# Prova02.net
KiCad netlist of a schematic drawn in EAGLE
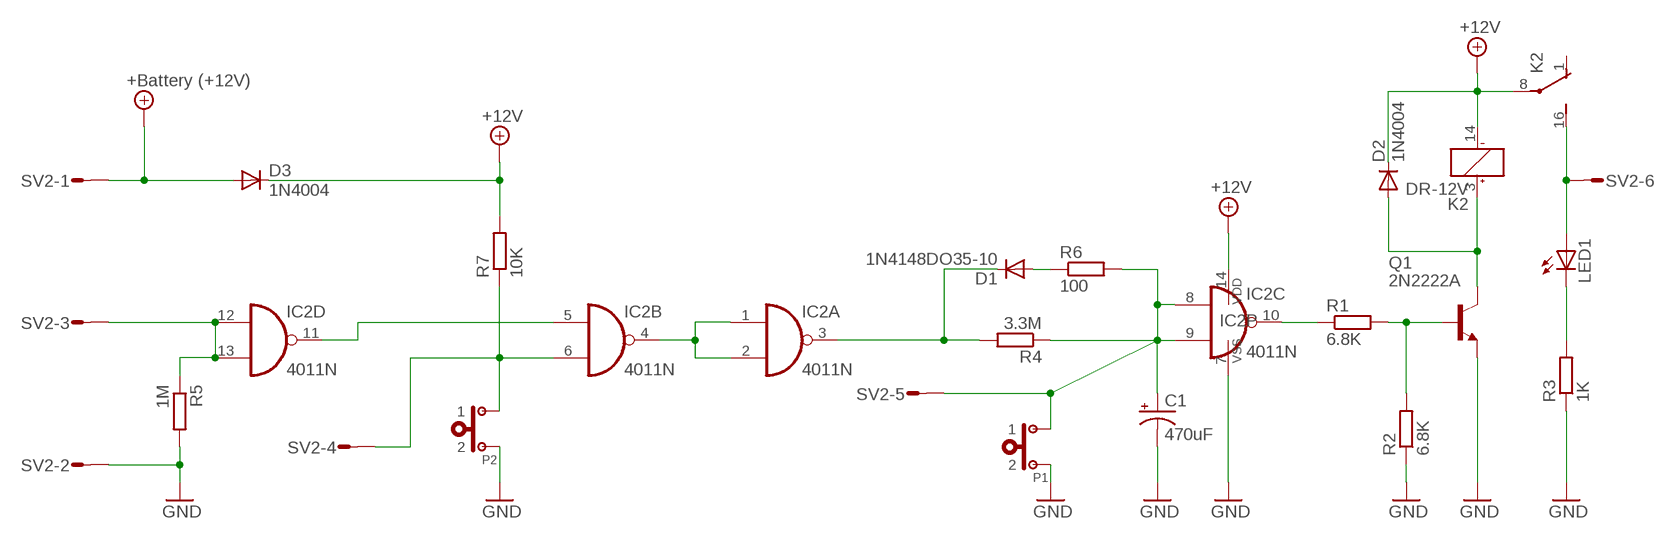
[diagram p0: schematic, sheet 1]

(export (version "E")
  (design (tool "Eeschema 10.0.6"))
  (components
    (comp (ref "C1")
      (value "470uF")
      (footprint "eagle-import:E3,5-8")
      (libsource (lib "eagle-import") (part "CPOL-USE3.5-8"))
    )
    (comp (ref "D1")
      (value "1N4148DO35-10")
      (footprint "eagle-import:DO35-10")
      (libsource (lib "eagle-import") (part "1N4148DO35-10"))
    )
    (comp (ref "D2")
      (value "1N4004")
      (footprint "eagle-import:DO41-10")
      (libsource (lib "eagle-import") (part "1N4004"))
    )
    (comp (ref "D3")
      (value "1N4004")
      (footprint "eagle-import:DO41-10")
      (libsource (lib "eagle-import") (part "1N4004"))
    )
    (comp (ref "IC2")
      (value "4011N")
      (footprint "eagle-import:DIL14")
      (libsource (lib "eagle-import") (part "4011N"))
    )
    (comp (ref "K2")
      (value "DR-12V")
      (footprint "eagle-import:DR-1")
      (libsource (lib "eagle-import") (part "DR-V12"))
    )
    (comp (ref "LED1")
      (value "LED")
      (footprint "eagle-import:SMARTLED-TTW")
      (libsource (lib "eagle-import") (part "LED"))
    )
    (comp (ref "P1")
      (value "PULSANTENO")
      (footprint "eagle-import:SIP02")
      (libsource (lib "eagle-import") (part "PULSANTENO"))
    )
    (comp (ref "P2")
      (value "PULSANTENO")
      (footprint "eagle-import:SIP02")
      (libsource (lib "eagle-import") (part "PULSANTENO"))
    )
    (comp (ref "Q1")
      (value "2N2222A")
      (footprint "eagle-import:TO18")
      (libsource (lib "eagle-import") (part "2N2222A"))
    )
    (comp (ref "R1")
      (value "6.8K")
      (footprint "eagle-import:0207_10")
      (libsource (lib "eagle-import") (part "R-EU_0207/10"))
    )
    (comp (ref "R2")
      (value "6.8K")
      (footprint "eagle-import:0207_10")
      (libsource (lib "eagle-import") (part "R-EU_0207/10"))
    )
    (comp (ref "R3")
      (value "1K")
      (footprint "eagle-import:0207_10")
      (libsource (lib "eagle-import") (part "R-EU_0207/10"))
    )
    (comp (ref "R4")
      (value "3.3M")
      (footprint "eagle-import:0207_10")
      (libsource (lib "eagle-import") (part "R-EU_0207/10"))
    )
    (comp (ref "R5")
      (value "1M")
      (footprint "eagle-import:0207_10")
      (libsource (lib "eagle-import") (part "R-EU_0207/10"))
    )
    (comp (ref "R6")
      (value "100")
      (footprint "eagle-import:0207_10")
      (libsource (lib "eagle-import") (part "R-EU_0207/10"))
    )
    (comp (ref "R7")
      (value "10K")
      (footprint "eagle-import:0207_10")
      (libsource (lib "eagle-import") (part "R-EU_0207/10"))
    )
    (comp (ref "SV2")
      (value "MT6-6")
      (footprint "eagle-import:MT6-6")
      (libsource (lib "eagle-import") (part "MT6-6"))
    )
  )
  (nets
    (net (code "1") (name "+12V") (class "Default")
      (node (ref "D2") (pin "C") (pinfunction "C_C") (pintype "passive"))
      (node (ref "D3") (pin "A") (pinfunction "A_A") (pintype "passive"))
      (node (ref "D3") (pin "C") (pinfunction "C_C") (pintype "passive"))
      (node (ref "IC2") (pin "14") (pinfunction "VDD_14") (pintype "power_in"))
      (node (ref "K2") (pin "14") (pinfunction "-_14") (pintype "passive"))
      (node (ref "K2") (pin "8") (pinfunction "P_8") (pintype "passive"))
      (node (ref "R7") (pin "2") (pinfunction "2_2") (pintype "passive"))
      (node (ref "SV2") (pin "1") (pinfunction "S_1") (pintype "passive"))
    )
    (net (code "2") (name "GND") (class "Default")
      (node (ref "C1") (pin "-") (pinfunction "-_-") (pintype "passive"))
      (node (ref "IC2") (pin "7") (pinfunction "VSS_7") (pintype "power_in"))
      (node (ref "P1") (pin "2") (pinfunction "2_2") (pintype "bidirectional"))
      (node (ref "P2") (pin "2") (pinfunction "2_2") (pintype "bidirectional"))
      (node (ref "Q1") (pin "1") (pinfunction "E_1") (pintype "passive"))
      (node (ref "R2") (pin "1") (pinfunction "1_1") (pintype "passive"))
      (node (ref "R3") (pin "1") (pinfunction "1_1") (pintype "passive"))
      (node (ref "R5") (pin "2") (pinfunction "2_2") (pintype "passive"))
      (node (ref "SV2") (pin "2") (pinfunction "S_2") (pintype "passive"))
    )
    (net (code "3") (name "Net-(D1-PadA)") (class "Default")
      (node (ref "D1") (pin "A") (pinfunction "A_A") (pintype "passive"))
      (node (ref "R6") (pin "1") (pinfunction "1_1") (pintype "passive"))
    )
    (net (code "4") (name "Net-(IC2A-I0)") (class "Default")
      (node (ref "IC2") (pin "1") (pinfunction "I0_1") (pintype "input"))
      (node (ref "IC2") (pin "2") (pinfunction "I1_2") (pintype "input"))
      (node (ref "IC2") (pin "4") (pinfunction "O_4") (pintype "output"))
    )
    (net (code "5") (name "Net-(IC2A-O)") (class "Default")
      (node (ref "D1") (pin "C") (pinfunction "C_C") (pintype "passive"))
      (node (ref "IC2") (pin "3") (pinfunction "O_3") (pintype "output"))
      (node (ref "R4") (pin "2") (pinfunction "2_2") (pintype "passive"))
    )
    (net (code "6") (name "Net-(IC2B-I0)") (class "Default")
      (node (ref "IC2") (pin "11") (pinfunction "O_11") (pintype "output"))
      (node (ref "IC2") (pin "5") (pinfunction "I0_5") (pintype "input"))
    )
    (net (code "7") (name "Net-(IC2B-I1)") (class "Default")
      (node (ref "IC2") (pin "6") (pinfunction "I1_6") (pintype "input"))
      (node (ref "P2") (pin "1") (pinfunction "1_1") (pintype "bidirectional"))
      (node (ref "R7") (pin "1") (pinfunction "1_1") (pintype "passive"))
      (node (ref "SV2") (pin "4") (pinfunction "S_4") (pintype "passive"))
    )
    (net (code "8") (name "Net-(IC2C-I0)") (class "Default")
      (node (ref "C1") (pin "+") (pinfunction "+_+") (pintype "passive"))
      (node (ref "IC2") (pin "8") (pinfunction "I0_8") (pintype "input"))
      (node (ref "IC2") (pin "9") (pinfunction "I1_9") (pintype "input"))
      (node (ref "P1") (pin "1") (pinfunction "1_1") (pintype "bidirectional"))
      (node (ref "R4") (pin "1") (pinfunction "1_1") (pintype "passive"))
      (node (ref "R6") (pin "2") (pinfunction "2_2") (pintype "passive"))
      (node (ref "SV2") (pin "5") (pinfunction "S_5") (pintype "passive"))
    )
    (net (code "9") (name "Net-(IC2C-O)") (class "Default")
      (node (ref "IC2") (pin "10") (pinfunction "O_10") (pintype "output"))
      (node (ref "R1") (pin "1") (pinfunction "1_1") (pintype "passive"))
    )
    (net (code "10") (name "Net-(IC2D-I0)") (class "Default")
      (node (ref "IC2") (pin "12") (pinfunction "I0_12") (pintype "input"))
      (node (ref "IC2") (pin "13") (pinfunction "I1_13") (pintype "input"))
      (node (ref "R5") (pin "1") (pinfunction "1_1") (pintype "passive"))
      (node (ref "SV2") (pin "3") (pinfunction "S_3") (pintype "passive"))
    )
    (net (code "11") (name "Net-(K2A-+)") (class "Default")
      (node (ref "D2") (pin "A") (pinfunction "A_A") (pintype "passive"))
      (node (ref "K2") (pin "3") (pinfunction "+_3") (pintype "passive"))
      (node (ref "Q1") (pin "3") (pinfunction "C_3") (pintype "passive"))
    )
    (net (code "12") (name "Net-(K2B-S)") (class "Default")
      (node (ref "K2") (pin "16") (pinfunction "S_16") (pintype "passive"))
      (node (ref "LED1") (pin "A@1") (pinfunction "A_A@1") (pintype "passive"))
      (node (ref "SV2") (pin "6") (pinfunction "S_6") (pintype "passive"))
    )
    (net (code "13") (name "Net-(LED1-C)") (class "Default")
      (node (ref "LED1") (pin "C@1") (pinfunction "C_C@1") (pintype "passive"))
      (node (ref "R3") (pin "2") (pinfunction "2_2") (pintype "passive"))
    )
    (net (code "14") (name "Net-(Q1-B)") (class "Default")
      (node (ref "Q1") (pin "2") (pinfunction "B_2") (pintype "passive"))
      (node (ref "R1") (pin "2") (pinfunction "2_2") (pintype "passive"))
      (node (ref "R2") (pin "2") (pinfunction "2_2") (pintype "passive"))
    )
    (net (code "15") (name "unconnected-(K2B-O-Pad1)") (class "Default")
      (node (ref "K2") (pin "1") (pinfunction "O_1") (pintype "passive"))
    )
  )
)
